# UwU_Bot.net
KiCad netlist of a schematic drawn in EAGLE
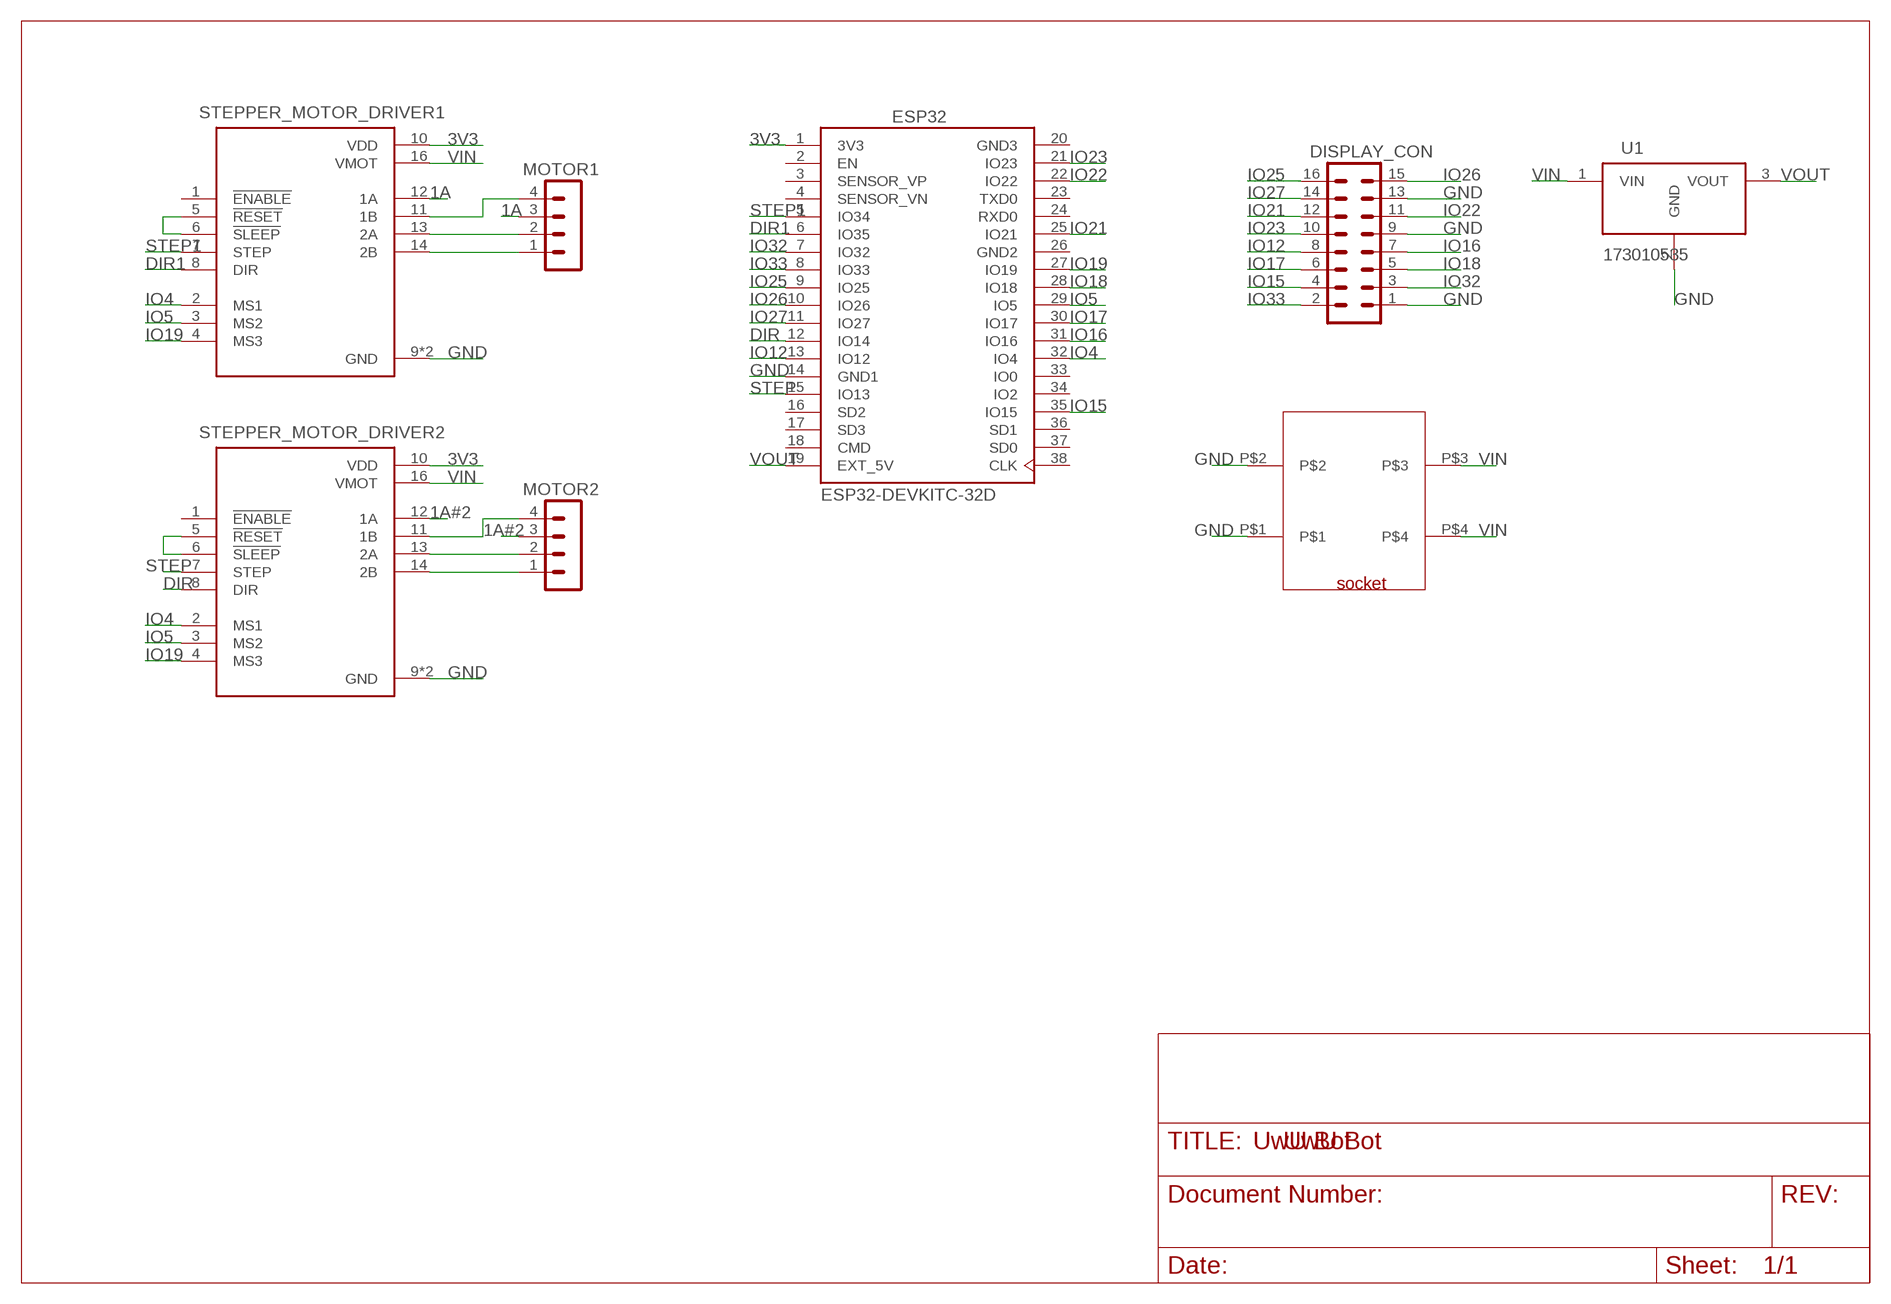
[diagram p0: schematic, sheet 1]

(export (version "E")
  (design (tool "Eeschema 10.0.6"))
  (components
    (comp (ref "DISPLAY_CON")
      (value "MA08-2")
      (footprint "eagle-import:MA08-2")
      (libsource (lib "eagle-import") (part "MA08-2"))
    )
    (comp (ref "ESP32")
      (value "ESP32-DEVKITC-32D")
      (footprint "eagle-import:MODULE_ESP32-DEVKITC-32D")
      (fields (field (name "MF") "Espressif Systems"))
      (libsource (lib "eagle-import") (part "ESP32-DEVKITC-32D"))
    )
    (comp (ref "MOTOR1")
      (value "MA04-1")
      (footprint "eagle-import:MA04-1")
      (libsource (lib "eagle-import") (part "MA04-1"))
    )
    (comp (ref "MOTOR2")
      (value "MA04-1")
      (footprint "eagle-import:MA04-1")
      (libsource (lib "eagle-import") (part "MA04-1"))
    )
    (comp (ref "STEPPER_MOTOR_DRIVER1")
      (value "A4988_STEPPER_MOTOR_DRIVER_CARRIER_BLACK")
      (footprint "eagle-import:MODULE_A4988_STEPPER_MOTOR_DRIVER_CARRIER_BLACK")
      (fields (field (name "MF") "Pololu") (field (name "MP") "A4988 STEPPER MOTOR DRIVER CARRIER BLACK"))
      (libsource (lib "eagle-import") (part "A4988_STEPPER_MOTOR_DRIVER_CARRIER_BLACK"))
    )
    (comp (ref "STEPPER_MOTOR_DRIVER2")
      (value "A4988_STEPPER_MOTOR_DRIVER_CARRIER_BLACK")
      (footprint "eagle-import:MODULE_A4988_STEPPER_MOTOR_DRIVER_CARRIER_BLACK")
      (fields (field (name "MF") "Pololu") (field (name "MP") "A4988 STEPPER MOTOR DRIVER CARRIER BLACK"))
      (libsource (lib "eagle-import") (part "A4988_STEPPER_MOTOR_DRIVER_CARRIER_BLACK"))
    )
    (comp (ref "U$1")
      (value "BUCHSEDC")
      (footprint "eagle-import:BUCHSE")
      (libsource (lib "eagle-import") (part "BUCHSEDC"))
    )
    (comp (ref "U1")
      (value "173010535")
      (footprint "eagle-import:173010535")
      (fields
        (field (name "DIGIKEY_PARTNO") "732-173010535-ND")
        (field (name "MANUFACTURER") "Würth Elektronik")
        (field (name "CREATED_BY") "PCBLayout.com")
      )
      (libsource (lib "eagle-import") (part "173010535"))
    )
  )
  (nets
    (net (code "1") (name "/1A") (class "Default")
      (node (ref "MOTOR1") (pin "3") (pinfunction "3_3") (pintype "passive"))
      (node (ref "STEPPER_MOTOR_DRIVER1") (pin "12") (pinfunction "1A_12") (pintype "output"))
    )
    (net (code "2") (name "/1A#2") (class "Default")
      (node (ref "MOTOR2") (pin "3") (pinfunction "3_3") (pintype "passive"))
      (node (ref "STEPPER_MOTOR_DRIVER2") (pin "12") (pinfunction "1A_12") (pintype "output"))
    )
    (net (code "3") (name "/3V3") (class "Default")
      (node (ref "ESP32") (pin "1") (pinfunction "3V3_1") (pintype "power_in"))
      (node (ref "STEPPER_MOTOR_DRIVER1") (pin "10") (pinfunction "VDD_10") (pintype "power_in"))
      (node (ref "STEPPER_MOTOR_DRIVER2") (pin "10") (pinfunction "VDD_10") (pintype "power_in"))
    )
    (net (code "4") (name "/DIR") (class "Default")
      (node (ref "ESP32") (pin "12") (pinfunction "IO14_12") (pintype "bidirectional"))
      (node (ref "STEPPER_MOTOR_DRIVER2") (pin "8") (pinfunction "DIR_8") (pintype "input"))
    )
    (net (code "5") (name "/DIR1") (class "Default")
      (node (ref "ESP32") (pin "6") (pinfunction "IO35_6") (pintype "bidirectional"))
      (node (ref "STEPPER_MOTOR_DRIVER1") (pin "8") (pinfunction "DIR_8") (pintype "input"))
    )
    (net (code "6") (name "/GND") (class "Default")
      (node (ref "DISPLAY_CON") (pin "1") (pinfunction "1_1") (pintype "passive"))
      (node (ref "DISPLAY_CON") (pin "13") (pinfunction "13_13") (pintype "passive"))
      (node (ref "DISPLAY_CON") (pin "9") (pinfunction "9_9") (pintype "passive"))
      (node (ref "ESP32") (pin "14") (pinfunction "GND1_14") (pintype "power_in"))
      (node (ref "STEPPER_MOTOR_DRIVER1") (pin "15") (pinfunction "GND_15") (pintype "power_in"))
      (node (ref "STEPPER_MOTOR_DRIVER1") (pin "9") (pinfunction "GND_9") (pintype "power_in"))
      (node (ref "STEPPER_MOTOR_DRIVER2") (pin "15") (pinfunction "GND_15") (pintype "power_in"))
      (node (ref "STEPPER_MOTOR_DRIVER2") (pin "9") (pinfunction "GND_9") (pintype "power_in"))
      (node (ref "U$1") (pin "P$1") (pinfunction "P$1_P$1") (pintype "bidirectional"))
      (node (ref "U$1") (pin "P$2") (pinfunction "P$2_P$2") (pintype "bidirectional"))
      (node (ref "U1") (pin "2") (pinfunction "GND_2") (pintype "power_in"))
    )
    (net (code "7") (name "/GND2") (class "Default")
      (node (ref "ESP32") (pin "26") (pinfunction "GND2_26") (pintype "power_in"))
    )
    (net (code "8") (name "/GND3") (class "Default")
      (node (ref "ESP32") (pin "20") (pinfunction "GND3_20") (pintype "power_in"))
    )
    (net (code "9") (name "/IO4") (class "Default")
      (node (ref "ESP32") (pin "32") (pinfunction "IO4_32") (pintype "bidirectional"))
      (node (ref "STEPPER_MOTOR_DRIVER1") (pin "2") (pinfunction "MS1_2") (pintype "input"))
      (node (ref "STEPPER_MOTOR_DRIVER2") (pin "2") (pinfunction "MS1_2") (pintype "input"))
    )
    (net (code "10") (name "/IO5") (class "Default")
      (node (ref "ESP32") (pin "29") (pinfunction "IO5_29") (pintype "bidirectional"))
      (node (ref "STEPPER_MOTOR_DRIVER1") (pin "3") (pinfunction "MS2_3") (pintype "input"))
      (node (ref "STEPPER_MOTOR_DRIVER2") (pin "3") (pinfunction "MS2_3") (pintype "input"))
    )
    (net (code "11") (name "/IO12") (class "Default")
      (node (ref "DISPLAY_CON") (pin "8") (pinfunction "8_8") (pintype "passive"))
      (node (ref "ESP32") (pin "13") (pinfunction "IO12_13") (pintype "bidirectional"))
    )
    (net (code "12") (name "/IO15") (class "Default")
      (node (ref "DISPLAY_CON") (pin "4") (pinfunction "4_4") (pintype "passive"))
      (node (ref "ESP32") (pin "35") (pinfunction "IO15_35") (pintype "bidirectional"))
    )
    (net (code "13") (name "/IO16") (class "Default")
      (node (ref "DISPLAY_CON") (pin "7") (pinfunction "7_7") (pintype "passive"))
      (node (ref "ESP32") (pin "31") (pinfunction "IO16_31") (pintype "bidirectional"))
    )
    (net (code "14") (name "/IO17") (class "Default")
      (node (ref "DISPLAY_CON") (pin "6") (pinfunction "6_6") (pintype "passive"))
      (node (ref "ESP32") (pin "30") (pinfunction "IO17_30") (pintype "bidirectional"))
    )
    (net (code "15") (name "/IO18") (class "Default")
      (node (ref "DISPLAY_CON") (pin "5") (pinfunction "5_5") (pintype "passive"))
      (node (ref "ESP32") (pin "28") (pinfunction "IO18_28") (pintype "bidirectional"))
    )
    (net (code "16") (name "/IO19") (class "Default")
      (node (ref "ESP32") (pin "27") (pinfunction "IO19_27") (pintype "bidirectional"))
      (node (ref "STEPPER_MOTOR_DRIVER1") (pin "4") (pinfunction "MS3_4") (pintype "input"))
      (node (ref "STEPPER_MOTOR_DRIVER2") (pin "4") (pinfunction "MS3_4") (pintype "input"))
    )
    (net (code "17") (name "/IO21") (class "Default")
      (node (ref "DISPLAY_CON") (pin "12") (pinfunction "12_12") (pintype "passive"))
      (node (ref "ESP32") (pin "25") (pinfunction "IO21_25") (pintype "bidirectional"))
    )
    (net (code "18") (name "/IO22") (class "Default")
      (node (ref "DISPLAY_CON") (pin "11") (pinfunction "11_11") (pintype "passive"))
      (node (ref "ESP32") (pin "22") (pinfunction "IO22_22") (pintype "bidirectional"))
    )
    (net (code "19") (name "/IO23") (class "Default")
      (node (ref "DISPLAY_CON") (pin "10") (pinfunction "10_10") (pintype "passive"))
      (node (ref "ESP32") (pin "21") (pinfunction "IO23_21") (pintype "bidirectional"))
    )
    (net (code "20") (name "/IO25") (class "Default")
      (node (ref "DISPLAY_CON") (pin "16") (pinfunction "16_16") (pintype "passive"))
      (node (ref "ESP32") (pin "9") (pinfunction "IO25_9") (pintype "bidirectional"))
    )
    (net (code "21") (name "/IO26") (class "Default")
      (node (ref "DISPLAY_CON") (pin "15") (pinfunction "15_15") (pintype "passive"))
      (node (ref "ESP32") (pin "10") (pinfunction "IO26_10") (pintype "bidirectional"))
    )
    (net (code "22") (name "/IO27") (class "Default")
      (node (ref "DISPLAY_CON") (pin "14") (pinfunction "14_14") (pintype "passive"))
      (node (ref "ESP32") (pin "11") (pinfunction "IO27_11") (pintype "bidirectional"))
    )
    (net (code "23") (name "/IO32") (class "Default")
      (node (ref "DISPLAY_CON") (pin "3") (pinfunction "3_3") (pintype "passive"))
      (node (ref "ESP32") (pin "7") (pinfunction "IO32_7") (pintype "bidirectional"))
    )
    (net (code "24") (name "/IO33") (class "Default")
      (node (ref "DISPLAY_CON") (pin "2") (pinfunction "2_2") (pintype "passive"))
      (node (ref "ESP32") (pin "8") (pinfunction "IO33_8") (pintype "bidirectional"))
    )
    (net (code "25") (name "/STEP") (class "Default")
      (node (ref "ESP32") (pin "15") (pinfunction "IO13_15") (pintype "bidirectional"))
      (node (ref "STEPPER_MOTOR_DRIVER2") (pin "7") (pinfunction "STEP_7") (pintype "input"))
    )
    (net (code "26") (name "/STEP1") (class "Default")
      (node (ref "ESP32") (pin "5") (pinfunction "IO34_5") (pintype "bidirectional"))
      (node (ref "STEPPER_MOTOR_DRIVER1") (pin "7") (pinfunction "STEP_7") (pintype "input"))
    )
    (net (code "27") (name "/VIN") (class "Default")
      (node (ref "STEPPER_MOTOR_DRIVER1") (pin "16") (pinfunction "VMOT_16") (pintype "power_in"))
      (node (ref "STEPPER_MOTOR_DRIVER2") (pin "16") (pinfunction "VMOT_16") (pintype "power_in"))
      (node (ref "U$1") (pin "P$3") (pinfunction "P$3_P$3") (pintype "bidirectional"))
      (node (ref "U$1") (pin "P$4") (pinfunction "P$4_P$4") (pintype "bidirectional"))
      (node (ref "U1") (pin "1") (pinfunction "VIN_1") (pintype "power_in"))
    )
    (net (code "28") (name "/VOUT") (class "Default")
      (node (ref "ESP32") (pin "19") (pinfunction "EXT_5V_19") (pintype "power_in"))
      (node (ref "U1") (pin "3") (pinfunction "VOUT_3") (pintype "power_in"))
    )
    (net (code "29") (name "Net-(STEPPER_MOTOR_DRIVER1-1B)") (class "Default")
      (node (ref "MOTOR1") (pin "4") (pinfunction "4_4") (pintype "passive"))
      (node (ref "STEPPER_MOTOR_DRIVER1") (pin "11") (pinfunction "1B_11") (pintype "output"))
    )
    (net (code "30") (name "Net-(STEPPER_MOTOR_DRIVER1-2A)") (class "Default")
      (node (ref "MOTOR1") (pin "2") (pinfunction "2_2") (pintype "passive"))
      (node (ref "STEPPER_MOTOR_DRIVER1") (pin "13") (pinfunction "2A_13") (pintype "output"))
    )
    (net (code "31") (name "Net-(STEPPER_MOTOR_DRIVER1-2B)") (class "Default")
      (node (ref "MOTOR1") (pin "1") (pinfunction "1_1") (pintype "passive"))
      (node (ref "STEPPER_MOTOR_DRIVER1") (pin "14") (pinfunction "2B_14") (pintype "output"))
    )
    (net (code "32") (name "Net-(STEPPER_MOTOR_DRIVER1-~{RESET})") (class "Default")
      (node (ref "STEPPER_MOTOR_DRIVER1") (pin "5") (pinfunction "~{RESET}_5") (pintype "input"))
      (node (ref "STEPPER_MOTOR_DRIVER1") (pin "6") (pinfunction "~{SLEEP}_6") (pintype "input"))
    )
    (net (code "33") (name "Net-(STEPPER_MOTOR_DRIVER2-1B)") (class "Default")
      (node (ref "MOTOR2") (pin "4") (pinfunction "4_4") (pintype "passive"))
      (node (ref "STEPPER_MOTOR_DRIVER2") (pin "11") (pinfunction "1B_11") (pintype "output"))
    )
    (net (code "34") (name "Net-(STEPPER_MOTOR_DRIVER2-2A)") (class "Default")
      (node (ref "MOTOR2") (pin "2") (pinfunction "2_2") (pintype "passive"))
      (node (ref "STEPPER_MOTOR_DRIVER2") (pin "13") (pinfunction "2A_13") (pintype "output"))
    )
    (net (code "35") (name "Net-(STEPPER_MOTOR_DRIVER2-2B)") (class "Default")
      (node (ref "MOTOR2") (pin "1") (pinfunction "1_1") (pintype "passive"))
      (node (ref "STEPPER_MOTOR_DRIVER2") (pin "14") (pinfunction "2B_14") (pintype "output"))
    )
    (net (code "36") (name "Net-(STEPPER_MOTOR_DRIVER2-~{RESET})") (class "Default")
      (node (ref "STEPPER_MOTOR_DRIVER2") (pin "5") (pinfunction "~{RESET}_5") (pintype "input"))
      (node (ref "STEPPER_MOTOR_DRIVER2") (pin "6") (pinfunction "~{SLEEP}_6") (pintype "input"))
    )
    (net (code "37") (name "unconnected-(ESP32-CLK-Pad38)") (class "Default")
      (node (ref "ESP32") (pin "38") (pinfunction "CLK_38") (pintype "input"))
    )
    (net (code "38") (name "unconnected-(ESP32-CMD-Pad18)") (class "Default")
      (node (ref "ESP32") (pin "18") (pinfunction "CMD_18") (pintype "bidirectional"))
    )
    (net (code "39") (name "unconnected-(ESP32-EN-Pad2)") (class "Default")
      (node (ref "ESP32") (pin "2") (pinfunction "EN_2") (pintype "input"))
    )
    (net (code "40") (name "unconnected-(ESP32-IO0-Pad33)") (class "Default")
      (node (ref "ESP32") (pin "33") (pinfunction "IO0_33") (pintype "bidirectional"))
    )
    (net (code "41") (name "unconnected-(ESP32-IO2-Pad34)") (class "Default")
      (node (ref "ESP32") (pin "34") (pinfunction "IO2_34") (pintype "bidirectional"))
    )
    (net (code "42") (name "unconnected-(ESP32-RXD0-Pad24)") (class "Default")
      (node (ref "ESP32") (pin "24") (pinfunction "RXD0_24") (pintype "input"))
    )
    (net (code "43") (name "unconnected-(ESP32-SD0-Pad37)") (class "Default")
      (node (ref "ESP32") (pin "37") (pinfunction "SD0_37") (pintype "bidirectional"))
    )
    (net (code "44") (name "unconnected-(ESP32-SD1-Pad36)") (class "Default")
      (node (ref "ESP32") (pin "36") (pinfunction "SD1_36") (pintype "bidirectional"))
    )
    (net (code "45") (name "unconnected-(ESP32-SD2-Pad16)") (class "Default")
      (node (ref "ESP32") (pin "16") (pinfunction "SD2_16") (pintype "bidirectional"))
    )
    (net (code "46") (name "unconnected-(ESP32-SD3-Pad17)") (class "Default")
      (node (ref "ESP32") (pin "17") (pinfunction "SD3_17") (pintype "bidirectional"))
    )
    (net (code "47") (name "unconnected-(ESP32-SENSOR_VN-Pad4)") (class "Default")
      (node (ref "ESP32") (pin "4") (pinfunction "SENSOR_VN_4") (pintype "input"))
    )
    (net (code "48") (name "unconnected-(ESP32-SENSOR_VP-Pad3)") (class "Default")
      (node (ref "ESP32") (pin "3") (pinfunction "SENSOR_VP_3") (pintype "input"))
    )
    (net (code "49") (name "unconnected-(ESP32-TXD0-Pad23)") (class "Default")
      (node (ref "ESP32") (pin "23") (pinfunction "TXD0_23") (pintype "output"))
    )
    (net (code "50") (name "unconnected-(STEPPER_MOTOR_DRIVER1-~{ENABLE}-Pad1)") (class "Default")
      (node (ref "STEPPER_MOTOR_DRIVER1") (pin "1") (pinfunction "~{ENABLE}_1") (pintype "input"))
    )
    (net (code "51") (name "unconnected-(STEPPER_MOTOR_DRIVER2-~{ENABLE}-Pad1)") (class "Default")
      (node (ref "STEPPER_MOTOR_DRIVER2") (pin "1") (pinfunction "~{ENABLE}_1") (pintype "input"))
    )
  )
)
